# epoch-rev-a.net
KiCad netlist of a schematic drawn in EAGLE
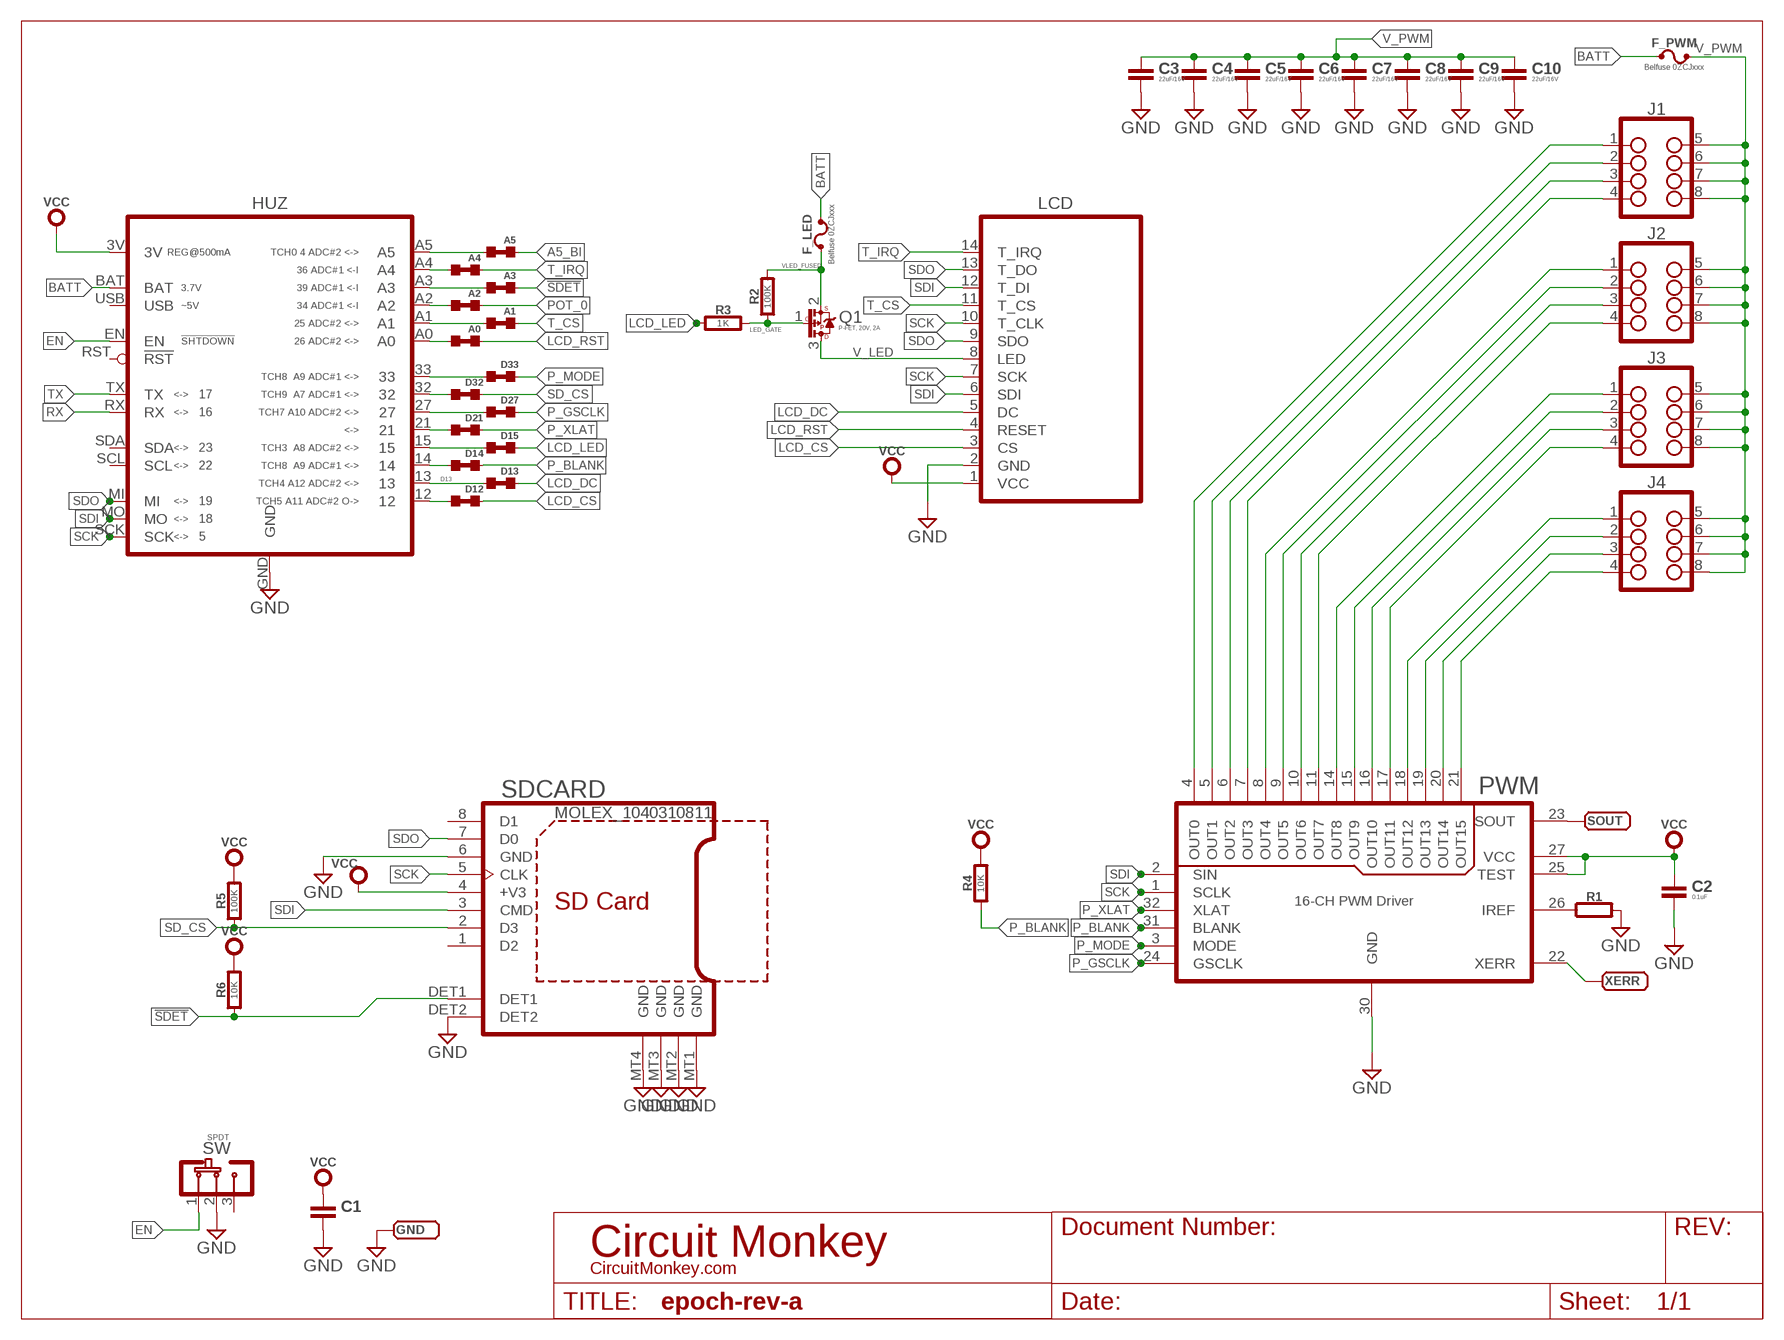
[diagram p0: schematic, sheet 1]

(export (version "E")
  (design (tool "Eeschema 10.0.6"))
  (components
    (comp (ref "A0")
      (value "NP")
      (footprint "eagle-import:0603-SHORT")
      (libsource (lib "eagle-import") (part "SHORT0603"))
    )
    (comp (ref "A1")
      (value "NP")
      (footprint "eagle-import:0603-SHORT")
      (libsource (lib "eagle-import") (part "SHORT0603"))
    )
    (comp (ref "A2")
      (value "NP")
      (footprint "eagle-import:0603-SHORT")
      (libsource (lib "eagle-import") (part "SHORT0603"))
    )
    (comp (ref "A3")
      (value "NP")
      (footprint "eagle-import:0603-SHORT")
      (libsource (lib "eagle-import") (part "SHORT0603"))
    )
    (comp (ref "A4")
      (value "NP")
      (footprint "eagle-import:0603-SHORT")
      (libsource (lib "eagle-import") (part "SHORT0603"))
    )
    (comp (ref "A5")
      (value "NP")
      (footprint "eagle-import:0603-SHORT")
      (libsource (lib "eagle-import") (part "SHORT0603"))
    )
    (comp (ref "C1")
      (value "CAPACITOR0603")
      (footprint "eagle-import:0603-CAP")
      (libsource (lib "eagle-import") (part "CAPACITOR0603"))
    )
    (comp (ref "C2")
      (value "0.1uF")
      (footprint "eagle-import:0603-CAP")
      (libsource (lib "eagle-import") (part "CAPACITOR0603"))
    )
    (comp (ref "C3")
      (value "22uF/16V")
      (footprint "eagle-import:1210-CAP")
      (libsource (lib "eagle-import") (part "CAPACITOR1210"))
    )
    (comp (ref "C4")
      (value "22uF/16V")
      (footprint "eagle-import:1210-CAP")
      (libsource (lib "eagle-import") (part "CAPACITOR1210"))
    )
    (comp (ref "C5")
      (value "22uF/16V")
      (footprint "eagle-import:1210-CAP")
      (libsource (lib "eagle-import") (part "CAPACITOR1210"))
    )
    (comp (ref "C6")
      (value "22uF/16V")
      (footprint "eagle-import:1210-CAP")
      (libsource (lib "eagle-import") (part "CAPACITOR1210"))
    )
    (comp (ref "C7")
      (value "22uF/16V")
      (footprint "eagle-import:1210-CAP")
      (libsource (lib "eagle-import") (part "CAPACITOR1210"))
    )
    (comp (ref "C8")
      (value "22uF/16V")
      (footprint "eagle-import:1210-CAP")
      (libsource (lib "eagle-import") (part "CAPACITOR1210"))
    )
    (comp (ref "C9")
      (value "22uF/16V")
      (footprint "eagle-import:1210-CAP")
      (libsource (lib "eagle-import") (part "CAPACITOR1210"))
    )
    (comp (ref "C10")
      (value "22uF/16V")
      (footprint "eagle-import:1210-CAP")
      (libsource (lib "eagle-import") (part "CAPACITOR1210"))
    )
    (comp (ref "D12")
      (value "NP")
      (footprint "eagle-import:0603-SHORT")
      (libsource (lib "eagle-import") (part "SHORT0603"))
    )
    (comp (ref "D13")
      (value "NP")
      (footprint "eagle-import:0603-SHORT")
      (libsource (lib "eagle-import") (part "SHORT0603"))
    )
    (comp (ref "D14")
      (value "NP")
      (footprint "eagle-import:0603-SHORT")
      (libsource (lib "eagle-import") (part "SHORT0603"))
    )
    (comp (ref "D15")
      (value "NP")
      (footprint "eagle-import:0603-SHORT")
      (libsource (lib "eagle-import") (part "SHORT0603"))
    )
    (comp (ref "D21")
      (value "NP")
      (footprint "eagle-import:0603-SHORT")
      (libsource (lib "eagle-import") (part "SHORT0603"))
    )
    (comp (ref "D27")
      (value "NP")
      (footprint "eagle-import:0603-SHORT")
      (libsource (lib "eagle-import") (part "SHORT0603"))
    )
    (comp (ref "D32")
      (value "NP")
      (footprint "eagle-import:0603-SHORT")
      (libsource (lib "eagle-import") (part "SHORT0603"))
    )
    (comp (ref "D33")
      (value "NP")
      (footprint "eagle-import:0603-SHORT")
      (libsource (lib "eagle-import") (part "SHORT0603"))
    )
    (comp (ref "F_LED")
      (value "Belfuse 0ZCJxxx")
      (footprint "eagle-import:BELFUSE-1206")
      (libsource (lib "eagle-import") (part "FUSEPOLY-1206"))
    )
    (comp (ref "F_PWM")
      (value "Belfuse 0ZCJxxx")
      (footprint "eagle-import:BELFUSE-1206")
      (libsource (lib "eagle-import") (part "FUSEPOLY-1206"))
    )
    (comp (ref "GND")
      (value "PADSMD-050X050")
      (footprint "eagle-import:SMD-050X050")
      (libsource (lib "eagle-import") (part "PADSMD-050X050"))
    )
    (comp (ref "HUZ")
      (value "HUZZAHHUZZAH")
      (footprint "eagle-import:ADAFRUIT_HUZZAH32")
      (libsource (lib "eagle-import") (part "HUZZAHHUZZAH"))
    )
    (comp (ref "J1")
      (value "NANOFIT-08P-DR-RA-THD")
      (footprint "eagle-import:MOLEX-105314-XX08")
      (libsource (lib "eagle-import") (part "NANOFIT-08P-DR-RA-THD"))
    )
    (comp (ref "J2")
      (value "NANOFIT-08P-DR-RA-THD")
      (footprint "eagle-import:MOLEX-105314-XX08")
      (libsource (lib "eagle-import") (part "NANOFIT-08P-DR-RA-THD"))
    )
    (comp (ref "J3")
      (value "NANOFIT-08P-DR-RA-THD")
      (footprint "eagle-import:MOLEX-105314-XX08")
      (libsource (lib "eagle-import") (part "NANOFIT-08P-DR-RA-THD"))
    )
    (comp (ref "J4")
      (value "NANOFIT-08P-DR-RA-THD")
      (footprint "eagle-import:MOLEX-105314-XX08")
      (libsource (lib "eagle-import") (part "NANOFIT-08P-DR-RA-THD"))
    )
    (comp (ref "LCD")
      (value "LCD-320X240-3.2-INCH-SPI-DIANN-LOWPROFILE")
      (footprint "eagle-import:LCD-320X240-DIANN-3.2-LP-SOCKET")
      (libsource (lib "eagle-import") (part "LCD-320X240-3.2-INCH-SPI-DIANN-LOWPROFILE"))
    )
    (comp (ref "PWM")
      (value "16-CH PWM Driver")
      (footprint "eagle-import:QFN-32")
      (fields (field (name "MFR") "Texas Instruments") (field (name "MPN") "TLC59401RHB"))
      (libsource (lib "eagle-import") (part "TLC59401-QFN"))
    )
    (comp (ref "Q1")
      (value "P-FET, 20V, 2A")
      (footprint "eagle-import:SOT-23")
      (fields (field (name "MPN") "FDN340P"))
      (libsource (lib "eagle-import") (part "P-FETSOT-23-2A"))
    )
    (comp (ref "R1")
      (value "RESISTOR0603")
      (footprint "eagle-import:0603-RES")
      (libsource (lib "eagle-import") (part "RESISTOR0603"))
    )
    (comp (ref "R2")
      (value "100K")
      (footprint "eagle-import:0603-RES")
      (libsource (lib "eagle-import") (part "RESISTOR0603"))
    )
    (comp (ref "R3")
      (value "1K")
      (footprint "eagle-import:0603-RES")
      (libsource (lib "eagle-import") (part "RESISTOR0603"))
    )
    (comp (ref "R4")
      (value "10K")
      (footprint "eagle-import:0603-RES")
      (libsource (lib "eagle-import") (part "RESISTOR0603"))
    )
    (comp (ref "R5")
      (value "100K")
      (footprint "eagle-import:0603-RES")
      (libsource (lib "eagle-import") (part "RESISTOR0603"))
    )
    (comp (ref "R6")
      (value "10K")
      (footprint "eagle-import:0603-RES")
      (libsource (lib "eagle-import") (part "RESISTOR0603"))
    )
    (comp (ref "SDCARD")
      (value "MOLEX_1040310811")
      (footprint "eagle-import:MOLEX_1040310811_USD")
      (fields (field (name "MFR") "Molex") (field (name "MPN") "1040310811"))
      (libsource (lib "eagle-import") (part "MICRO-SD-CARDMOLEX-1040310811"))
    )
    (comp (ref "SOUT")
      (value "PADSMD-050X050")
      (footprint "eagle-import:SMD-050X050")
      (libsource (lib "eagle-import") (part "PADSMD-050X050"))
    )
    (comp (ref "SW")
      (value "SPDT")
      (footprint "eagle-import:CK_TS01C")
      (fields (field (name "MFR") "C&K") (field (name "MPN") "TS01C*"))
      (libsource (lib "eagle-import") (part "SLIDE-SPDTCK_TS01"))
    )
    (comp (ref "XERR")
      (value "PADSMD-050X050")
      (footprint "eagle-import:SMD-050X050")
      (libsource (lib "eagle-import") (part "PADSMD-050X050"))
    )
  )
  (nets
    (net (code "1") (name "/D13") (class "Default")
      (node (ref "D13") (pin "3") (pinfunction "1_3") (pintype "passive"))
      (node (ref "HUZ") (pin "13") (pinfunction "13_13") (pintype "bidirectional"))
    )
    (net (code "2") (name "/LED_GATE") (class "Default")
      (node (ref "Q1") (pin "1") (pinfunction "G_1") (pintype "bidirectional"))
      (node (ref "R2") (pin "1") (pinfunction "1_1") (pintype "passive"))
      (node (ref "R3") (pin "2") (pinfunction "2_2") (pintype "passive"))
    )
    (net (code "3") (name "/VLED_FUSED") (class "Default")
      (node (ref "F_LED") (pin "1") (pinfunction "1_1") (pintype "bidirectional"))
      (node (ref "Q1") (pin "2") (pinfunction "S_2") (pintype "bidirectional"))
      (node (ref "R2") (pin "2") (pinfunction "2_2") (pintype "passive"))
    )
    (net (code "4") (name "/V_LED") (class "Default")
      (node (ref "LCD") (pin "8") (pinfunction "LED_8") (pintype "bidirectional"))
      (node (ref "Q1") (pin "3") (pinfunction "D_3") (pintype "bidirectional"))
    )
    (net (code "5") (name "/~{SDET}") (class "Default")
      (node (ref "A3") (pin "4") (pinfunction "2_4") (pintype "passive"))
      (node (ref "R6") (pin "1") (pinfunction "1_1") (pintype "passive"))
      (node (ref "SDCARD") (pin "DET1") (pinfunction "DET1_DET1") (pintype "passive"))
    )
    (net (code "6") (name "A5_BI") (class "Default")
      (node (ref "A5") (pin "4") (pinfunction "2_4") (pintype "passive"))
    )
    (net (code "7") (name "BATT") (class "Default")
      (node (ref "F_LED") (pin "2") (pinfunction "2_2") (pintype "bidirectional"))
      (node (ref "F_PWM") (pin "1") (pinfunction "1_1") (pintype "bidirectional"))
      (node (ref "HUZ") (pin "BAT") (pinfunction "BAT_BAT") (pintype "bidirectional"))
    )
    (net (code "8") (name "EN") (class "Default")
      (node (ref "HUZ") (pin "EN") (pinfunction "EN_EN") (pintype "bidirectional"))
      (node (ref "SW") (pin "1") (pinfunction "A_1") (pintype "bidirectional"))
    )
    (net (code "9") (name "GND") (class "Default")
      (node (ref "C1") (pin "2") (pinfunction "2_2") (pintype "passive"))
      (node (ref "C10") (pin "2") (pinfunction "2_2") (pintype "passive"))
      (node (ref "C2") (pin "2") (pinfunction "2_2") (pintype "passive"))
      (node (ref "C3") (pin "2") (pinfunction "2_2") (pintype "passive"))
      (node (ref "C4") (pin "2") (pinfunction "2_2") (pintype "passive"))
      (node (ref "C5") (pin "2") (pinfunction "2_2") (pintype "passive"))
      (node (ref "C6") (pin "2") (pinfunction "2_2") (pintype "passive"))
      (node (ref "C7") (pin "2") (pinfunction "2_2") (pintype "passive"))
      (node (ref "C8") (pin "2") (pinfunction "2_2") (pintype "passive"))
      (node (ref "C9") (pin "2") (pinfunction "2_2") (pintype "passive"))
      (node (ref "GND") (pin "1") (pinfunction "PAD_1") (pintype "bidirectional"))
      (node (ref "HUZ") (pin "GND") (pinfunction "GND_GND") (pintype "bidirectional"))
      (node (ref "LCD") (pin "2") (pinfunction "GND_2") (pintype "bidirectional"))
      (node (ref "PWM") (pin "30") (pinfunction "GND_30") (pintype "power_in"))
      (node (ref "R1") (pin "2") (pinfunction "2_2") (pintype "passive"))
      (node (ref "SDCARD") (pin "6") (pinfunction "GND_6") (pintype "power_in"))
      (node (ref "SDCARD") (pin "DET2") (pinfunction "DET2_DET2") (pintype "passive"))
      (node (ref "SDCARD") (pin "MT1") (pinfunction "GND_MT1") (pintype "power_in"))
      (node (ref "SDCARD") (pin "MT2") (pinfunction "GND_MT2") (pintype "power_in"))
      (node (ref "SDCARD") (pin "MT3") (pinfunction "GND_MT3") (pintype "power_in"))
      (node (ref "SDCARD") (pin "MT4") (pinfunction "GND_MT4") (pintype "power_in"))
      (node (ref "SW") (pin "2") (pinfunction "C_2") (pintype "bidirectional"))
    )
    (net (code "10") (name "LCD_CS") (class "Default")
      (node (ref "D12") (pin "4") (pinfunction "2_4") (pintype "passive"))
      (node (ref "LCD") (pin "3") (pinfunction "CS_3") (pintype "bidirectional"))
    )
    (net (code "11") (name "LCD_DC") (class "Default")
      (node (ref "D13") (pin "4") (pinfunction "2_4") (pintype "passive"))
      (node (ref "LCD") (pin "5") (pinfunction "DC_5") (pintype "bidirectional"))
    )
    (net (code "12") (name "LCD_LED") (class "Default")
      (node (ref "D15") (pin "4") (pinfunction "2_4") (pintype "passive"))
      (node (ref "R3") (pin "1") (pinfunction "1_1") (pintype "passive"))
    )
    (net (code "13") (name "LCD_RST") (class "Default")
      (node (ref "A0") (pin "4") (pinfunction "2_4") (pintype "passive"))
      (node (ref "LCD") (pin "4") (pinfunction "RESET_4") (pintype "bidirectional"))
    )
    (net (code "14") (name "Net-(A0-1)") (class "Default")
      (node (ref "A0") (pin "3") (pinfunction "1_3") (pintype "passive"))
      (node (ref "HUZ") (pin "A0") (pinfunction "A0_A0") (pintype "bidirectional"))
    )
    (net (code "15") (name "Net-(A1-1)") (class "Default")
      (node (ref "A1") (pin "3") (pinfunction "1_3") (pintype "passive"))
      (node (ref "HUZ") (pin "A1") (pinfunction "A1_A1") (pintype "bidirectional"))
    )
    (net (code "16") (name "Net-(A2-1)") (class "Default")
      (node (ref "A2") (pin "3") (pinfunction "1_3") (pintype "passive"))
      (node (ref "HUZ") (pin "A2") (pinfunction "A2_A2") (pintype "bidirectional"))
    )
    (net (code "17") (name "Net-(A3-1)") (class "Default")
      (node (ref "A3") (pin "3") (pinfunction "1_3") (pintype "passive"))
      (node (ref "HUZ") (pin "A3") (pinfunction "A3_A3") (pintype "bidirectional"))
    )
    (net (code "18") (name "Net-(A4-1)") (class "Default")
      (node (ref "A4") (pin "3") (pinfunction "1_3") (pintype "passive"))
      (node (ref "HUZ") (pin "A4") (pinfunction "A4_A4") (pintype "bidirectional"))
    )
    (net (code "19") (name "Net-(A5-1)") (class "Default")
      (node (ref "A5") (pin "3") (pinfunction "1_3") (pintype "passive"))
      (node (ref "HUZ") (pin "A5") (pinfunction "A5_A5") (pintype "bidirectional"))
    )
    (net (code "20") (name "Net-(D12-1)") (class "Default")
      (node (ref "D12") (pin "3") (pinfunction "1_3") (pintype "passive"))
      (node (ref "HUZ") (pin "12") (pinfunction "12_12") (pintype "bidirectional"))
    )
    (net (code "21") (name "Net-(D14-1)") (class "Default")
      (node (ref "D14") (pin "3") (pinfunction "1_3") (pintype "passive"))
      (node (ref "HUZ") (pin "14") (pinfunction "14_14") (pintype "bidirectional"))
    )
    (net (code "22") (name "Net-(D15-1)") (class "Default")
      (node (ref "D15") (pin "3") (pinfunction "1_3") (pintype "passive"))
      (node (ref "HUZ") (pin "15") (pinfunction "15_15") (pintype "bidirectional"))
    )
    (net (code "23") (name "Net-(D21-1)") (class "Default")
      (node (ref "D21") (pin "3") (pinfunction "1_3") (pintype "passive"))
      (node (ref "HUZ") (pin "21") (pinfunction "21_21") (pintype "bidirectional"))
    )
    (net (code "24") (name "Net-(D27-1)") (class "Default")
      (node (ref "D27") (pin "3") (pinfunction "1_3") (pintype "passive"))
      (node (ref "HUZ") (pin "27") (pinfunction "27_27") (pintype "bidirectional"))
    )
    (net (code "25") (name "Net-(D32-1)") (class "Default")
      (node (ref "D32") (pin "3") (pinfunction "1_3") (pintype "passive"))
      (node (ref "HUZ") (pin "32") (pinfunction "32_32") (pintype "bidirectional"))
    )
    (net (code "26") (name "Net-(D33-1)") (class "Default")
      (node (ref "D33") (pin "3") (pinfunction "1_3") (pintype "passive"))
      (node (ref "HUZ") (pin "33") (pinfunction "33_33") (pintype "bidirectional"))
    )
    (net (code "27") (name "Net-(PWM-IREF)") (class "Default")
      (node (ref "PWM") (pin "26") (pinfunction "IREF_26") (pintype "passive"))
      (node (ref "R1") (pin "1") (pinfunction "1_1") (pintype "passive"))
    )
    (net (code "28") (name "Net-(PWM-OUT0)") (class "Default")
      (node (ref "J1") (pin "1") (pinfunction "1_1") (pintype "bidirectional"))
      (node (ref "PWM") (pin "4") (pinfunction "OUT0_4") (pintype "open_collector"))
    )
    (net (code "29") (name "Net-(PWM-OUT1)") (class "Default")
      (node (ref "J1") (pin "2") (pinfunction "2_2") (pintype "bidirectional"))
      (node (ref "PWM") (pin "5") (pinfunction "OUT1_5") (pintype "open_collector"))
    )
    (net (code "30") (name "Net-(PWM-OUT2)") (class "Default")
      (node (ref "J1") (pin "3") (pinfunction "3_3") (pintype "bidirectional"))
      (node (ref "PWM") (pin "6") (pinfunction "OUT2_6") (pintype "open_collector"))
    )
    (net (code "31") (name "Net-(PWM-OUT3)") (class "Default")
      (node (ref "J1") (pin "4") (pinfunction "4_4") (pintype "bidirectional"))
      (node (ref "PWM") (pin "7") (pinfunction "OUT3_7") (pintype "open_collector"))
    )
    (net (code "32") (name "Net-(PWM-OUT4)") (class "Default")
      (node (ref "J2") (pin "1") (pinfunction "1_1") (pintype "bidirectional"))
      (node (ref "PWM") (pin "8") (pinfunction "OUT4_8") (pintype "open_collector"))
    )
    (net (code "33") (name "Net-(PWM-OUT5)") (class "Default")
      (node (ref "J2") (pin "2") (pinfunction "2_2") (pintype "bidirectional"))
      (node (ref "PWM") (pin "9") (pinfunction "OUT5_9") (pintype "open_collector"))
    )
    (net (code "34") (name "Net-(PWM-OUT6)") (class "Default")
      (node (ref "J2") (pin "3") (pinfunction "3_3") (pintype "bidirectional"))
      (node (ref "PWM") (pin "10") (pinfunction "OUT6_10") (pintype "open_collector"))
    )
    (net (code "35") (name "Net-(PWM-OUT7)") (class "Default")
      (node (ref "J2") (pin "4") (pinfunction "4_4") (pintype "bidirectional"))
      (node (ref "PWM") (pin "11") (pinfunction "OUT7_11") (pintype "open_collector"))
    )
    (net (code "36") (name "Net-(PWM-OUT8)") (class "Default")
      (node (ref "J3") (pin "1") (pinfunction "1_1") (pintype "bidirectional"))
      (node (ref "PWM") (pin "14") (pinfunction "OUT8_14") (pintype "open_collector"))
    )
    (net (code "37") (name "Net-(PWM-OUT9)") (class "Default")
      (node (ref "J3") (pin "2") (pinfunction "2_2") (pintype "bidirectional"))
      (node (ref "PWM") (pin "15") (pinfunction "OUT9_15") (pintype "open_collector"))
    )
    (net (code "38") (name "Net-(PWM-OUT10)") (class "Default")
      (node (ref "J3") (pin "3") (pinfunction "3_3") (pintype "bidirectional"))
      (node (ref "PWM") (pin "16") (pinfunction "OUT10_16") (pintype "open_collector"))
    )
    (net (code "39") (name "Net-(PWM-OUT11)") (class "Default")
      (node (ref "J3") (pin "4") (pinfunction "4_4") (pintype "bidirectional"))
      (node (ref "PWM") (pin "17") (pinfunction "OUT11_17") (pintype "open_collector"))
    )
    (net (code "40") (name "Net-(PWM-OUT12)") (class "Default")
      (node (ref "J4") (pin "1") (pinfunction "1_1") (pintype "bidirectional"))
      (node (ref "PWM") (pin "18") (pinfunction "OUT12_18") (pintype "open_collector"))
    )
    (net (code "41") (name "Net-(PWM-OUT13)") (class "Default")
      (node (ref "J4") (pin "2") (pinfunction "2_2") (pintype "bidirectional"))
      (node (ref "PWM") (pin "19") (pinfunction "OUT13_19") (pintype "open_collector"))
    )
    (net (code "42") (name "Net-(PWM-OUT14)") (class "Default")
      (node (ref "J4") (pin "3") (pinfunction "3_3") (pintype "bidirectional"))
      (node (ref "PWM") (pin "20") (pinfunction "OUT14_20") (pintype "open_collector"))
    )
    (net (code "43") (name "Net-(PWM-OUT15)") (class "Default")
      (node (ref "J4") (pin "4") (pinfunction "4_4") (pintype "bidirectional"))
      (node (ref "PWM") (pin "21") (pinfunction "OUT15_21") (pintype "open_collector"))
    )
    (net (code "44") (name "Net-(PWM-SOUT)") (class "Default")
      (node (ref "PWM") (pin "23") (pinfunction "SOUT_23") (pintype "output"))
      (node (ref "SOUT") (pin "1") (pinfunction "PAD_1") (pintype "bidirectional"))
    )
    (net (code "45") (name "Net-(PWM-XERR)") (class "Default")
      (node (ref "PWM") (pin "22") (pinfunction "XERR_22") (pintype "output"))
      (node (ref "XERR") (pin "1") (pinfunction "PAD_1") (pintype "bidirectional"))
    )
    (net (code "46") (name "POT_0") (class "Default")
      (node (ref "A2") (pin "4") (pinfunction "2_4") (pintype "passive"))
    )
    (net (code "47") (name "P_BLANK") (class "Default")
      (node (ref "D14") (pin "4") (pinfunction "2_4") (pintype "passive"))
      (node (ref "PWM") (pin "31") (pinfunction "BLANK_31") (pintype "input"))
      (node (ref "R4") (pin "1") (pinfunction "1_1") (pintype "passive"))
    )
    (net (code "48") (name "P_GSCLK") (class "Default")
      (node (ref "D27") (pin "4") (pinfunction "2_4") (pintype "passive"))
      (node (ref "PWM") (pin "24") (pinfunction "GSCLK_24") (pintype "input"))
    )
    (net (code "49") (name "P_MODE") (class "Default")
      (node (ref "D33") (pin "4") (pinfunction "2_4") (pintype "passive"))
      (node (ref "PWM") (pin "3") (pinfunction "MODE_3") (pintype "input"))
    )
    (net (code "50") (name "P_XLAT") (class "Default")
      (node (ref "D21") (pin "4") (pinfunction "2_4") (pintype "passive"))
      (node (ref "PWM") (pin "32") (pinfunction "XLAT_32") (pintype "input"))
    )
    (net (code "51") (name "RX") (class "Default")
      (node (ref "HUZ") (pin "RX") (pinfunction "RX_RX") (pintype "bidirectional"))
    )
    (net (code "52") (name "SCK") (class "Default")
      (node (ref "HUZ") (pin "SCK") (pinfunction "SCK_SCK") (pintype "bidirectional"))
      (node (ref "LCD") (pin "10") (pinfunction "T_CLK_10") (pintype "bidirectional"))
      (node (ref "LCD") (pin "7") (pinfunction "SCK_7") (pintype "bidirectional"))
      (node (ref "PWM") (pin "1") (pinfunction "SCLK_1") (pintype "input"))
      (node (ref "SDCARD") (pin "5") (pinfunction "CLK_5") (pintype "input"))
    )
    (net (code "53") (name "SDI") (class "Default")
      (node (ref "HUZ") (pin "MO") (pinfunction "MO_MO") (pintype "bidirectional"))
      (node (ref "LCD") (pin "12") (pinfunction "T_DI_12") (pintype "bidirectional"))
      (node (ref "LCD") (pin "6") (pinfunction "SDI_6") (pintype "bidirectional"))
      (node (ref "PWM") (pin "2") (pinfunction "SIN_2") (pintype "input"))
      (node (ref "SDCARD") (pin "3") (pinfunction "CMD_3") (pintype "bidirectional"))
    )
    (net (code "54") (name "SDO") (class "Default")
      (node (ref "HUZ") (pin "MI") (pinfunction "MI_MI") (pintype "bidirectional"))
      (node (ref "LCD") (pin "13") (pinfunction "T_DO_13") (pintype "bidirectional"))
      (node (ref "LCD") (pin "9") (pinfunction "SDO_9") (pintype "bidirectional"))
      (node (ref "SDCARD") (pin "7") (pinfunction "D0_7") (pintype "bidirectional"))
    )
    (net (code "55") (name "SD_CS") (class "Default")
      (node (ref "D32") (pin "4") (pinfunction "2_4") (pintype "passive"))
      (node (ref "R5") (pin "1") (pinfunction "1_1") (pintype "passive"))
      (node (ref "SDCARD") (pin "2") (pinfunction "D3_2") (pintype "bidirectional"))
    )
    (net (code "56") (name "TX") (class "Default")
      (node (ref "HUZ") (pin "TX") (pinfunction "TX_TX") (pintype "bidirectional"))
    )
    (net (code "57") (name "T_CS") (class "Default")
      (node (ref "A1") (pin "4") (pinfunction "2_4") (pintype "passive"))
      (node (ref "LCD") (pin "11") (pinfunction "T_CS_11") (pintype "bidirectional"))
    )
    (net (code "58") (name "T_IRQ") (class "Default")
      (node (ref "A4") (pin "4") (pinfunction "2_4") (pintype "passive"))
      (node (ref "LCD") (pin "14") (pinfunction "T_IRQ_14") (pintype "bidirectional"))
    )
    (net (code "59") (name "VCC") (class "Default")
      (node (ref "C1") (pin "1") (pinfunction "1_1") (pintype "passive"))
      (node (ref "C2") (pin "1") (pinfunction "1_1") (pintype "passive"))
      (node (ref "HUZ") (pin "3V") (pinfunction "3V_3V") (pintype "bidirectional"))
      (node (ref "LCD") (pin "1") (pinfunction "VCC_1") (pintype "bidirectional"))
      (node (ref "PWM") (pin "25") (pinfunction "TEST_25") (pintype "input"))
      (node (ref "PWM") (pin "27") (pinfunction "VCC_27") (pintype "power_in"))
      (node (ref "R4") (pin "2") (pinfunction "2_2") (pintype "passive"))
      (node (ref "R5") (pin "2") (pinfunction "2_2") (pintype "passive"))
      (node (ref "R6") (pin "2") (pinfunction "2_2") (pintype "passive"))
      (node (ref "SDCARD") (pin "4") (pinfunction "+V3_4") (pintype "power_in"))
    )
    (net (code "60") (name "V_PWM") (class "Default")
      (node (ref "C10") (pin "1") (pinfunction "1_1") (pintype "passive"))
      (node (ref "C3") (pin "1") (pinfunction "1_1") (pintype "passive"))
      (node (ref "C4") (pin "1") (pinfunction "1_1") (pintype "passive"))
      (node (ref "C5") (pin "1") (pinfunction "1_1") (pintype "passive"))
      (node (ref "C6") (pin "1") (pinfunction "1_1") (pintype "passive"))
      (node (ref "C7") (pin "1") (pinfunction "1_1") (pintype "passive"))
      (node (ref "C8") (pin "1") (pinfunction "1_1") (pintype "passive"))
      (node (ref "C9") (pin "1") (pinfunction "1_1") (pintype "passive"))
      (node (ref "F_PWM") (pin "2") (pinfunction "2_2") (pintype "bidirectional"))
      (node (ref "J1") (pin "5") (pinfunction "5_5") (pintype "bidirectional"))
      (node (ref "J1") (pin "6") (pinfunction "6_6") (pintype "bidirectional"))
      (node (ref "J1") (pin "7") (pinfunction "7_7") (pintype "bidirectional"))
      (node (ref "J1") (pin "8") (pinfunction "8_8") (pintype "bidirectional"))
      (node (ref "J2") (pin "5") (pinfunction "5_5") (pintype "bidirectional"))
      (node (ref "J2") (pin "6") (pinfunction "6_6") (pintype "bidirectional"))
      (node (ref "J2") (pin "7") (pinfunction "7_7") (pintype "bidirectional"))
      (node (ref "J2") (pin "8") (pinfunction "8_8") (pintype "bidirectional"))
      (node (ref "J3") (pin "5") (pinfunction "5_5") (pintype "bidirectional"))
      (node (ref "J3") (pin "6") (pinfunction "6_6") (pintype "bidirectional"))
      (node (ref "J3") (pin "7") (pinfunction "7_7") (pintype "bidirectional"))
      (node (ref "J3") (pin "8") (pinfunction "8_8") (pintype "bidirectional"))
      (node (ref "J4") (pin "5") (pinfunction "5_5") (pintype "bidirectional"))
      (node (ref "J4") (pin "6") (pinfunction "6_6") (pintype "bidirectional"))
      (node (ref "J4") (pin "7") (pinfunction "7_7") (pintype "bidirectional"))
      (node (ref "J4") (pin "8") (pinfunction "8_8") (pintype "bidirectional"))
    )
    (net (code "61") (name "unconnected-(HUZ-PadSCL)") (class "Default")
      (node (ref "HUZ") (pin "SCL") (pinfunction "SCL_SCL") (pintype "bidirectional"))
    )
    (net (code "62") (name "unconnected-(HUZ-PadSDA)") (class "Default")
      (node (ref "HUZ") (pin "SDA") (pinfunction "SDA_SDA") (pintype "bidirectional"))
    )
    (net (code "63") (name "unconnected-(HUZ-PadUSB)") (class "Default")
      (node (ref "HUZ") (pin "USB") (pinfunction "USB_USB") (pintype "bidirectional"))
    )
    (net (code "64") (name "unconnected-(HUZ-~{RST}-PadRST)") (class "Default")
      (node (ref "HUZ") (pin "RST") (pinfunction "~{RST}_RST") (pintype "bidirectional"))
    )
    (net (code "65") (name "unconnected-(SDCARD-D1-Pad8)") (class "Default")
      (node (ref "SDCARD") (pin "8") (pinfunction "D1_8") (pintype "bidirectional"))
    )
    (net (code "66") (name "unconnected-(SDCARD-D2-Pad1)") (class "Default")
      (node (ref "SDCARD") (pin "1") (pinfunction "D2_1") (pintype "bidirectional"))
    )
    (net (code "67") (name "unconnected-(SW-B-Pad3)") (class "Default")
      (node (ref "SW") (pin "3") (pinfunction "B_3") (pintype "bidirectional"))
    )
  )
)
